# 2025210236.net
KiCad netlist of a schematic drawn in EasyEDA Pro
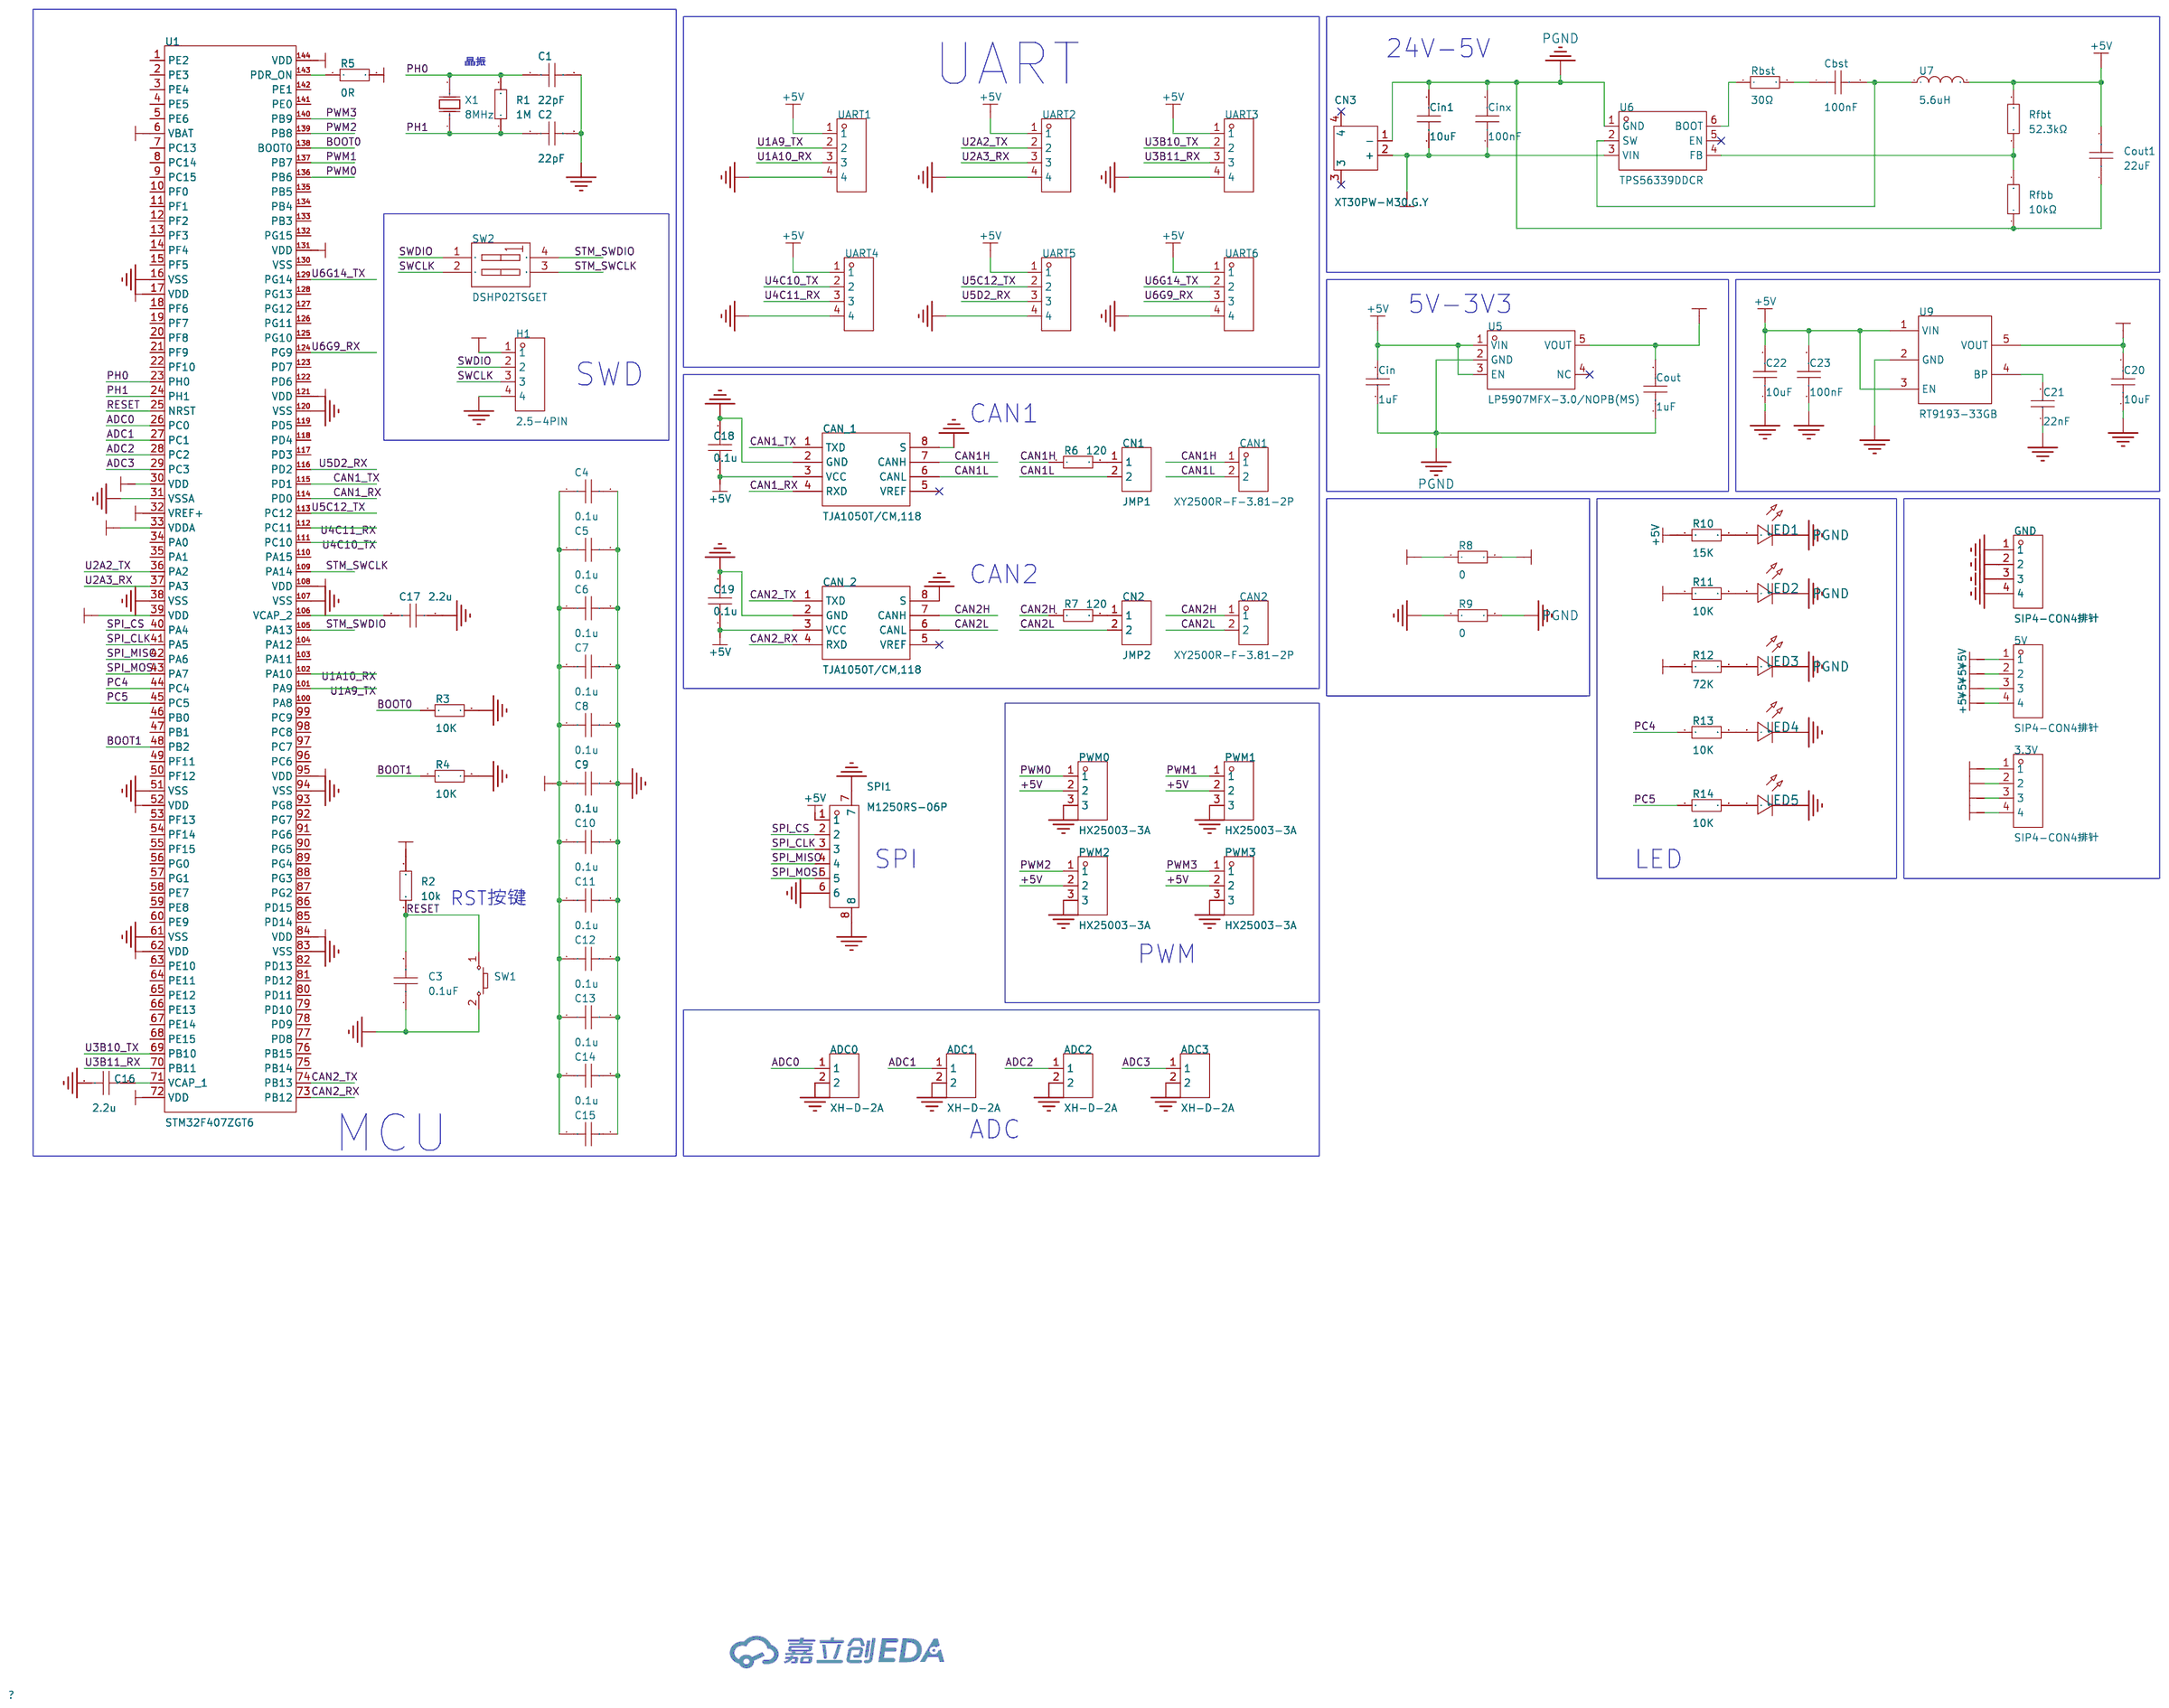
[diagram p0: schematic sheet]

(export (version "E")
  (design (tool "Eeschema 10.0.6"))
  (components
    (comp (ref "3.3V")
      (value "SIP4-CON4排针")
      (footprint "easyedapro:HDR-TH_4P-P2.54-V-M-3")
      (libsource (lib "easyedapro") (part "SIP4-CON4排针"))
    )
    (comp (ref "5V")
      (value "SIP4-CON4排针")
      (footprint "easyedapro:HDR-TH_4P-P2.54-V-M-3")
      (libsource (lib "easyedapro") (part "SIP4-CON4排针"))
    )
    (comp (ref "ADC0")
      (value "XH-D-2A")
      (footprint "easyedapro:CONN-TH_XH-2A")
      (fields (field (name "Manufacturer") "DEALON(德艺隆)"))
      (libsource (lib "easyedapro") (part "XH-D-2A"))
    )
    (comp (ref "ADC1")
      (value "XH-D-2A")
      (footprint "easyedapro:CONN-TH_XH-2A")
      (fields (field (name "Manufacturer") "DEALON(德艺隆)"))
      (libsource (lib "easyedapro") (part "XH-D-2A"))
    )
    (comp (ref "ADC2")
      (value "XH-D-2A")
      (footprint "easyedapro:CONN-TH_XH-2A")
      (fields (field (name "Manufacturer") "DEALON(德艺隆)"))
      (libsource (lib "easyedapro") (part "XH-D-2A"))
    )
    (comp (ref "ADC3")
      (value "XH-D-2A")
      (footprint "easyedapro:CONN-TH_XH-2A")
      (fields (field (name "Manufacturer") "DEALON(德艺隆)"))
      (libsource (lib "easyedapro") (part "XH-D-2A"))
    )
    (comp (ref "C1")
      (value "22pF")
      (footprint "easyedapro:C0603")
      (libsource (lib "easyedapro") (part "Capacitance"))
    )
    (comp (ref "C2")
      (value "22pF")
      (footprint "easyedapro:C0603")
      (libsource (lib "easyedapro") (part "Capacitance"))
    )
    (comp (ref "C3")
      (value "0.1uF")
      (footprint "easyedapro:C0603")
      (libsource (lib "easyedapro") (part "Capacitance"))
    )
    (comp (ref "C4")
      (value "0.1u")
      (footprint "easyedapro:C0603")
      (libsource (lib "easyedapro") (part "Capacitance"))
    )
    (comp (ref "C5")
      (value "0.1u")
      (footprint "easyedapro:C0603")
      (libsource (lib "easyedapro") (part "Capacitance"))
    )
    (comp (ref "C6")
      (value "0.1u")
      (footprint "easyedapro:C0603")
      (libsource (lib "easyedapro") (part "Capacitance"))
    )
    (comp (ref "C7")
      (value "0.1u")
      (footprint "easyedapro:C0603")
      (libsource (lib "easyedapro") (part "Capacitance"))
    )
    (comp (ref "C8")
      (value "0.1u")
      (footprint "easyedapro:C0603")
      (libsource (lib "easyedapro") (part "Capacitance"))
    )
    (comp (ref "C9")
      (value "0.1u")
      (footprint "easyedapro:C0603")
      (libsource (lib "easyedapro") (part "Capacitance"))
    )
    (comp (ref "C10")
      (value "0.1u")
      (footprint "easyedapro:C0603")
      (libsource (lib "easyedapro") (part "Capacitance"))
    )
    (comp (ref "C11")
      (value "0.1u")
      (footprint "easyedapro:C0603")
      (libsource (lib "easyedapro") (part "Capacitance"))
    )
    (comp (ref "C12")
      (value "0.1u")
      (footprint "easyedapro:C0603")
      (libsource (lib "easyedapro") (part "Capacitance"))
    )
    (comp (ref "C13")
      (value "0.1u")
      (footprint "easyedapro:C0603")
      (libsource (lib "easyedapro") (part "Capacitance"))
    )
    (comp (ref "C14")
      (value "0.1u")
      (footprint "easyedapro:C0603")
      (libsource (lib "easyedapro") (part "Capacitance"))
    )
    (comp (ref "C15")
      (value "0.1u")
      (footprint "easyedapro:C0603")
      (libsource (lib "easyedapro") (part "Capacitance"))
    )
    (comp (ref "C16")
      (value "2.2u")
      (footprint "easyedapro:C0603")
      (libsource (lib "easyedapro") (part "Capacitance"))
    )
    (comp (ref "C17")
      (value "2.2u")
      (footprint "easyedapro:C0603")
      (libsource (lib "easyedapro") (part "Capacitance"))
    )
    (comp (ref "C18")
      (value "0.1u")
      (footprint "easyedapro:C0603")
      (libsource (lib "easyedapro") (part "Capacitance"))
    )
    (comp (ref "C19")
      (value "0.1u")
      (footprint "easyedapro:C0603")
      (libsource (lib "easyedapro") (part "Capacitance"))
    )
    (comp (ref "C20")
      (value "10uF")
      (footprint "easyedapro:C0603")
      (description "容值:10uF;精度:±10%;额定电压:10V;温度系数:X5R;")
      (fields
        (field (name "Manufacturer Part") "CGA0603X5R106K100JT")
        (field (name "Manufacturer") "HRE(芯声)")
      )
      (libsource (lib "easyedapro") (part "CGA0603X5R106K100JT"))
    )
    (comp (ref "C21")
      (value "22nF")
      (footprint "easyedapro:C0603")
      (description "容值:22nF;精度:±10%;额定电压:50V;温度系数:X7R;")
      (fields
        (field (name "Manufacturer Part") "CL10B223KB8NNNC")
        (field (name "Manufacturer") "SAMSUNG(三星)")
      )
      (libsource (lib "easyedapro") (part "CL10B223KB8NNNC"))
    )
    (comp (ref "C22")
      (value "10uF")
      (footprint "easyedapro:C0603")
      (description "容值:10uF;精度:±10%;额定电压:10V;温度系数:X5R;")
      (fields
        (field (name "Manufacturer Part") "CGA0603X5R106K100JT")
        (field (name "Manufacturer") "HRE(芯声)")
      )
      (libsource (lib "easyedapro") (part "CGA0603X5R106K100JT"))
    )
    (comp (ref "C23")
      (value "100nF")
      (footprint "easyedapro:C0603")
      (description "容值:100nF;精度:±10%;额定电压:50V;温度系数:X7R;")
      (fields
        (field (name "Manufacturer Part") "CGA0603X7R104K500JT")
        (field (name "Manufacturer") "HRE(芯声)")
      )
      (libsource (lib "easyedapro") (part "CGA0603X7R104K500JT"))
    )
    (comp (ref "CAN1")
      (value "XY2500R-F-3.81-2P")
      (footprint "easyedapro:CONN-TH_XY2500R-F-3.81-2P")
      (description "连接器类型:板端/插座-闭口;结构:1x2P;间距:3.81mm;颜色:绿色;安装方式:弯针;排数:1;每排PIN数:2;额定电流:8A;额定电压:300V;工作温度:-;")
      (fields (field (name "Manufacturer") "XINLAIYA(新莱亚)"))
      (libsource (lib "easyedapro") (part "XY2500R-F-3.81-2P"))
    )
    (comp (ref "CAN2")
      (value "XY2500R-F-3.81-2P")
      (footprint "easyedapro:CONN-TH_XY2500R-F-3.81-2P")
      (description "连接器类型:板端/插座-闭口;结构:1x2P;间距:3.81mm;颜色:绿色;安装方式:弯针;排数:1;每排PIN数:2;额定电流:8A;额定电压:300V;工作温度:-;")
      (fields (field (name "Manufacturer") "XINLAIYA(新莱亚)"))
      (libsource (lib "easyedapro") (part "XY2500R-F-3.81-2P"))
    )
    (comp (ref "CAN_1")
      (value "TJA1050T/CM,118")
      (footprint "easyedapro:SOIC-8_L5.0-W4.0-P1.27-LS6.0-BL")
      (description "类型:-;")
      (fields (field (name "Manufacturer") "NXP(恩智浦)"))
      (libsource (lib "easyedapro") (part "TJA1050T/CM,118"))
    )
    (comp (ref "CAN_2")
      (value "TJA1050T/CM,118")
      (footprint "easyedapro:SOIC-8_L5.0-W4.0-P1.27-LS6.0-BL")
      (description "类型:-;")
      (fields (field (name "Manufacturer") "NXP(恩智浦)"))
      (libsource (lib "easyedapro") (part "TJA1050T/CM,118"))
    )
    (comp (ref "Cbst")
      (value "100nF")
      (footprint "easyedapro:C0805")
      (description "容值:100nF;精度:±20%;额定电压:50V;材质(温度系数):X7R;")
      (fields (field (name "Manufacturer Part") "C0805C104M5RACTU") (field (name "Manufacturer") "KEMET(基美)"))
      (libsource (lib "easyedapro") (part "C0805C104M5RACTU"))
    )
    (comp (ref "Cin")
      (value "1uF")
      (footprint "easyedapro:C0603")
      (description "容值:1uF;精度:±10%;额定电压:16V;温度系数:X7R;")
      (fields
        (field (name "Manufacturer Part") "EMK107B7105KA-T")
        (field (name "Manufacturer") "TAIYO YUDEN(太诱)")
      )
      (libsource (lib "easyedapro") (part "EMK107B7105KA-T"))
    )
    (comp (ref "Cin1")
      (value "10uF")
      (footprint "easyedapro:C0805")
      (description "容值:10uF;精度:±20%;额定电压:25V;温度系数:X5R;")
      (fields
        (field (name "Manufacturer Part") "MSAST21GBB5106MTNA01")
        (field (name "Manufacturer") "TAIYO YUDEN(太诱)")
      )
      (libsource (lib "easyedapro") (part "MSAST21GBB5106MTNA01"))
    )
    (comp (ref "Cinx")
      (value "100nF")
      (footprint "easyedapro:C0805")
      (description "容值:100nF;精度:±20%;额定电压:50V;材质(温度系数):X7R;")
      (fields (field (name "Manufacturer Part") "C0805C104M5RACTU") (field (name "Manufacturer") "KEMET(基美)"))
      (libsource (lib "easyedapro") (part "C0805C104M5RACTU"))
    )
    (comp (ref "CN1")
      (value "JMP1")
      (footprint "easyedapro:HDR-TH_2P-P2.54_C9900022687")
      (libsource (lib "easyedapro") (part "2.54MM间距 针长19MM 2P排针"))
    )
    (comp (ref "CN2")
      (value "JMP2")
      (footprint "easyedapro:HDR-TH_2P-P2.54_C9900022687")
      (libsource (lib "easyedapro") (part "2.54MM间距 针长19MM 2P排针"))
    )
    (comp (ref "CN3")
      (value "XT30PW-M30.G.Y")
      (footprint "easyedapro:CONN-TH_XT30PW-M")
      (description "类别:-;类型1:-;")
      (fields (field (name "Manufacturer") "AMASS(艾迈斯)"))
      (libsource (lib "easyedapro") (part "XT30PW-M"))
    )
    (comp (ref "Cout")
      (value "1uF")
      (footprint "easyedapro:C0402")
      (description "容值:1uF;精度:±10%;额定电压:25V;温度系数:X5R;")
      (fields (field (name "Manufacturer Part") "C1005X5R1E105K050BC") (field (name "Manufacturer") "TDK"))
      (libsource (lib "easyedapro") (part "C1005X5R1E105K050BC"))
    )
    (comp (ref "Cout1")
      (value "22uF")
      (footprint "easyedapro:C0805")
      (description "容值:22uF;精度:±20%;额定电压:10V;温度系数:X5R;")
      (fields (field (name "Manufacturer Part") "C2012X5R1A226M125AB") (field (name "Manufacturer") "TDK"))
      (libsource (lib "easyedapro") (part "C2012X5R1A226M125AB_C2167626"))
    )
    (comp (ref "GND")
      (value "SIP4-CON4排针")
      (footprint "easyedapro:HDR-TH_4P-P2.54-V-M-3")
      (libsource (lib "easyedapro") (part "SIP4-CON4排针"))
    )
    (comp (ref "H1")
      (value "2.5-4PIN")
      (footprint "easyedapro:HDR-TH_4P-P2.54-V-M")
      (libsource (lib "easyedapro") (part "2.5-4PIN"))
    )
    (comp (ref "LED1")
      (value "~")
      (footprint "easyedapro:LED_0603")
      (libsource (lib "easyedapro") (part "LED_R"))
    )
    (comp (ref "LED2")
      (value "~")
      (footprint "easyedapro:LED_0603")
      (libsource (lib "easyedapro") (part "LED_R"))
    )
    (comp (ref "LED3")
      (value "~")
      (footprint "easyedapro:LED_0603")
      (libsource (lib "easyedapro") (part "LED_R"))
    )
    (comp (ref "LED4")
      (value "~")
      (footprint "easyedapro:LED_0603")
      (libsource (lib "easyedapro") (part "LED_R"))
    )
    (comp (ref "LED5")
      (value "~")
      (footprint "easyedapro:LED_0603")
      (libsource (lib "easyedapro") (part "LED_R"))
    )
    (comp (ref "PWM0")
      (value "HX25003-3A")
      (footprint "easyedapro:CONN-TH_3P-P2.50_HX25003-3A")
      (description "插针结构:1x3P;间距:2.5mm;安装方式:直插;参考系列:XH;总PIN数:3P;排数:1;每排PIN数:3;行距:-;额定电流:5A;触头材质:黄铜;工作温度:-25°C~+85°C;")
      (fields (field (name "Manufacturer") "HX(红星)"))
      (libsource (lib "easyedapro") (part "HX25003-3A"))
    )
    (comp (ref "PWM1")
      (value "HX25003-3A")
      (footprint "easyedapro:CONN-TH_3P-P2.50_HX25003-3A")
      (description "插针结构:1x3P;间距:2.5mm;安装方式:直插;参考系列:XH;总PIN数:3P;排数:1;每排PIN数:3;行距:-;额定电流:5A;触头材质:黄铜;工作温度:-25°C~+85°C;")
      (fields (field (name "Manufacturer") "HX(红星)"))
      (libsource (lib "easyedapro") (part "HX25003-3A"))
    )
    (comp (ref "PWM2")
      (value "HX25003-3A")
      (footprint "easyedapro:CONN-TH_3P-P2.50_HX25003-3A")
      (description "插针结构:1x3P;间距:2.5mm;安装方式:直插;参考系列:XH;总PIN数:3P;排数:1;每排PIN数:3;行距:-;额定电流:5A;触头材质:黄铜;工作温度:-25°C~+85°C;")
      (fields (field (name "Manufacturer") "HX(红星)"))
      (libsource (lib "easyedapro") (part "HX25003-3A"))
    )
    (comp (ref "PWM3")
      (value "HX25003-3A")
      (footprint "easyedapro:CONN-TH_3P-P2.50_HX25003-3A")
      (description "插针结构:1x3P;间距:2.5mm;安装方式:直插;参考系列:XH;总PIN数:3P;排数:1;每排PIN数:3;行距:-;额定电流:5A;触头材质:黄铜;工作温度:-25°C~+85°C;")
      (fields (field (name "Manufacturer") "HX(红星)"))
      (libsource (lib "easyedapro") (part "HX25003-3A"))
    )
    (comp (ref "R1") (value "1M") (footprint "easyedapro:R0603") (libsource (lib "easyedapro") (part "电阻")))
    (comp (ref "R2") (value "10k") (footprint "easyedapro:R0603") (libsource (lib "easyedapro") (part "电阻")))
    (comp (ref "R3") (value "10K") (footprint "easyedapro:R0603") (libsource (lib "easyedapro") (part "电阻")))
    (comp (ref "R4") (value "10K") (footprint "easyedapro:R0603") (libsource (lib "easyedapro") (part "电阻")))
    (comp (ref "R5") (value "0R") (footprint "easyedapro:R0603") (libsource (lib "easyedapro") (part "电阻")))
    (comp (ref "R6") (value "120") (footprint "easyedapro:R0603") (libsource (lib "easyedapro") (part "电阻")))
    (comp (ref "R7") (value "120") (footprint "easyedapro:R0603") (libsource (lib "easyedapro") (part "电阻")))
    (comp (ref "R8") (value "0") (footprint "easyedapro:R0603") (libsource (lib "easyedapro") (part "电阻")))
    (comp (ref "R9") (value "0") (footprint "easyedapro:R0603") (libsource (lib "easyedapro") (part "电阻")))
    (comp (ref "R10") (value "15K") (footprint "easyedapro:R0603") (libsource (lib "easyedapro") (part "电阻")))
    (comp (ref "R11") (value "10K") (footprint "easyedapro:R0603") (libsource (lib "easyedapro") (part "电阻")))
    (comp (ref "R12") (value "72K") (footprint "easyedapro:R0603") (libsource (lib "easyedapro") (part "电阻")))
    (comp (ref "R13") (value "10K") (footprint "easyedapro:R0603") (libsource (lib "easyedapro") (part "电阻")))
    (comp (ref "R14") (value "10K") (footprint "easyedapro:R0603") (libsource (lib "easyedapro") (part "电阻")))
    (comp (ref "Rbst")
      (value "30Ω")
      (footprint "easyedapro:R0603")
      (description "电阻类型:厚膜电阻;阻值:30Ω;精度:±1%;功率:100mW;工作电压:75V;温度系数:±100ppm/°C;")
      (fields (field (name "Manufacturer Part") "RC0603FR-0730RL") (field (name "Manufacturer") "YAGEO(国巨)"))
      (libsource (lib "easyedapro") (part "RC0603FR-0730RL"))
    )
    (comp (ref "Rfbb")
      (value "10kΩ")
      (footprint "easyedapro:R0603")
      (description "电阻类型:厚膜电阻;阻值:10kΩ;精度:±1%;功率:100mW;最大工作电压:75V;温度系数:±100ppm/°C;")
      (fields (field (name "Manufacturer Part") "RC0603FR-0710KL") (field (name "Manufacturer") "YAGEO(国巨)"))
      (libsource (lib "easyedapro") (part "RC0603FR-0710KL"))
    )
    (comp (ref "Rfbt")
      (value "52.3kΩ")
      (footprint "easyedapro:R0603")
      (description "电阻类型:厚膜电阻;阻值:52.3kΩ;精度:±1%;功率:100mW;工作电压:75V;温度系数:±100ppm/°C;")
      (fields (field (name "Manufacturer Part") "RC0603FR-0752K3L") (field (name "Manufacturer") "YAGEO(国巨)"))
      (libsource (lib "easyedapro") (part "RC0603FR-0752K3L"))
    )
    (comp (ref "SPI1")
      (value "M1250RS-06P")
      (footprint "easyedapro:CONN-SMD_M1250RS-06P")
      (description "插针结构:1x6P;间距:1.25mm;安装方式:卧贴;参考系列:-;总PIN数:6P;排数:1;每排PIN数:6;行距:-;额定电流:1A;工作温度:-25°C~+85°C;")
      (fields (field (name "Manufacturer") "XFCN(兴飞)"))
      (libsource (lib "easyedapro") (part "M1250RS-06P"))
    )
    (comp (ref "SW1")
      (value "~")
      (footprint "easyedapro:Key_SMD_3x4x2")
      (libsource (lib "easyedapro") (part "轻触按键x2"))
    )
    (comp (ref "SW2")
      (value "DSHP02TSGET")
      (footprint "easyedapro:SW-SMD_4P_DSHP02TSGET")
      (description "类型:平拨,凹槽式;电路结构:单刀单掷;开关位数:2位;工作寿命:-;颜色:黑色;")
      (fields (field (name "Manufacturer") "YE"))
      (libsource (lib "easyedapro") (part "DSHP02TSGET"))
    )
    (comp (ref "U1")
      (value "STM32F407ZGT6")
      (footprint "easyedapro:LQFP-144_L20.0-W20.0-P0.50-LS22.0-BL")
      (description "CPU内核:ARM-M4;CPU最大主频:168MHz;应用领域:-;")
      (fields (field (name "Manufacturer") "ST(意法半导体)"))
      (libsource (lib "easyedapro") (part "STM32F407ZGT6"))
    )
    (comp (ref "U5")
      (value "LP5907MFX-3.0/NOPB(MS)")
      (footprint "easyedapro:SOT-23-5_L2.9-W1.6-P0.95-LS2.8-BR")
      (description "输出类型:固定;最大输入电压:5.5V;输出电压:3V;输出电流:300mA;电源纹波抑制比(PSRR):-;输出极性:正极;")
      (fields (field (name "Manufacturer") "MSKSEMI(美森科)"))
      (libsource (lib "easyedapro") (part "LP5907MFX-3.0/NOPB(MS)"))
    )
    (comp (ref "U6")
      (value "TPS56339DDCR")
      (footprint "easyedapro:TSOT-23-6_L2.9-W1.6-P0.95-LS2.8-BR")
      (description "功能类型:降压型;输出类型:可调;输入电压:4.5V~24V;输出电压:800mV~16V;输出电流:3A;")
      (fields (field (name "Manufacturer") "TI(德州仪器)"))
      (libsource (lib "easyedapro") (part "TPS56339DDCR"))
    )
    (comp (ref "U7")
      (value "5.6uH")
      (footprint "easyedapro:IND-SMD_L13.0-W13.0-SDR1307-XXXXX")
      (description "电感值:5.6uH;精度:±20%;额定电流:6.5A;饱和电流(Isat):11A;类型:-;")
      (fields (field (name "Manufacturer Part") "SDR1307-5R6ML") (field (name "Manufacturer") "BOURNS"))
      (libsource (lib "easyedapro") (part "SDR1307-5R6ML"))
    )
    (comp (ref "U9")
      (value "RT9193-33GB")
      (footprint "easyedapro:SOT-23-5_L3.0-W1.7-P0.95-LS2.8-BL")
      (description "输出类型:固定;工作电压:5.5V;输出电压:3.3V;输出电流:300mA;电源纹波抑制比(PSRR):-50dB@(10kHz);输出极性:正极;")
      (fields (field (name "Manufacturer") "RICHTEK(立锜)"))
      (libsource (lib "easyedapro") (part "RT9193-33GB"))
    )
    (comp (ref "UART1")
      (value "SIP4-CON4排针")
      (footprint "easyedapro:HDR-TH_4P-P2.54-V-M-3")
      (libsource (lib "easyedapro") (part "SIP4-CON4排针"))
    )
    (comp (ref "UART2")
      (value "SIP4-CON4排针")
      (footprint "easyedapro:HDR-TH_4P-P2.54-V-M-3")
      (libsource (lib "easyedapro") (part "SIP4-CON4排针"))
    )
    (comp (ref "UART3")
      (value "SIP4-CON4排针")
      (footprint "easyedapro:HDR-TH_4P-P2.54-V-M-3")
      (libsource (lib "easyedapro") (part "SIP4-CON4排针"))
    )
    (comp (ref "UART4")
      (value "SIP4-CON4排针")
      (footprint "easyedapro:HDR-TH_4P-P2.54-V-M-3")
      (libsource (lib "easyedapro") (part "SIP4-CON4排针"))
    )
    (comp (ref "UART5")
      (value "SIP4-CON4排针")
      (footprint "easyedapro:HDR-TH_4P-P2.54-V-M-3")
      (libsource (lib "easyedapro") (part "SIP4-CON4排针"))
    )
    (comp (ref "UART6")
      (value "SIP4-CON4排针")
      (footprint "easyedapro:HDR-TH_4P-P2.54-V-M-3")
      (libsource (lib "easyedapro") (part "SIP4-CON4排针"))
    )
    (comp (ref "X1")
      (value "8MHz")
      (footprint "easyedapro:CRYSTAL-SMD_L5.0-W3.2")
      (description "晶振类型:贴片晶振;频率:8MHz;常温频差:±10ppm;负载电容:20pF;频率稳定度:±20ppm;")
      (fields (field (name "Manufacturer Part") "X50328MSB2GI") (field (name "Manufacturer") "YXC(扬兴晶振)"))
      (libsource (lib "easyedapro") (part "X50328MSB2GI"))
    )
  )
  (nets
    (net (code "1") (name "+5V") (class "Default")
      (node (ref "5V") (pin "1") (pinfunction "1_1") (pintype "unspecified"))
      (node (ref "5V") (pin "2") (pinfunction "2_2") (pintype "unspecified"))
      (node (ref "5V") (pin "3") (pinfunction "3_3") (pintype "unspecified"))
      (node (ref "5V") (pin "4") (pinfunction "4_4") (pintype "unspecified"))
      (node (ref "C18") (pin "1") (pinfunction "1_1") (pintype "input"))
      (node (ref "C19") (pin "1") (pinfunction "1_1") (pintype "input"))
      (node (ref "C22") (pin "2") (pinfunction "2_2") (pintype "unspecified"))
      (node (ref "C23") (pin "2") (pinfunction "2_2") (pintype "unspecified"))
      (node (ref "CAN_1") (pin "3") (pinfunction "VCC_3") (pintype "unspecified"))
      (node (ref "CAN_2") (pin "3") (pinfunction "VCC_3") (pintype "unspecified"))
      (node (ref "Cin") (pin "2") (pinfunction "2_2") (pintype "input"))
      (node (ref "Cout1") (pin "2") (pinfunction "2_2") (pintype "unspecified"))
      (node (ref "PWM0") (pin "2") (pinfunction "2_2") (pintype "unspecified"))
      (node (ref "PWM1") (pin "2") (pinfunction "2_2") (pintype "unspecified"))
      (node (ref "PWM2") (pin "2") (pinfunction "2_2") (pintype "unspecified"))
      (node (ref "PWM3") (pin "2") (pinfunction "2_2") (pintype "unspecified"))
      (node (ref "R10") (pin "1") (pinfunction "1_1") (pintype "input"))
      (node (ref "Rfbt") (pin "2") (pinfunction "2_2") (pintype "unspecified"))
      (node (ref "SPI1") (pin "1") (pinfunction "1_1") (pintype "unspecified"))
      (node (ref "U5") (pin "1") (pinfunction "VIN_1") (pintype "unspecified"))
      (node (ref "U5") (pin "3") (pinfunction "EN_3") (pintype "unspecified"))
      (node (ref "U7") (pin "2") (pinfunction "2_2") (pintype "unspecified"))
      (node (ref "U9") (pin "1") (pinfunction "VIN_1") (pintype "unspecified"))
      (node (ref "U9") (pin "3") (pinfunction "EN_3") (pintype "unspecified"))
      (node (ref "UART1") (pin "1") (pinfunction "1_1") (pintype "unspecified"))
      (node (ref "UART2") (pin "1") (pinfunction "1_1") (pintype "unspecified"))
      (node (ref "UART3") (pin "1") (pinfunction "1_1") (pintype "unspecified"))
      (node (ref "UART4") (pin "1") (pinfunction "1_1") (pintype "unspecified"))
      (node (ref "UART5") (pin "1") (pinfunction "1_1") (pintype "unspecified"))
      (node (ref "UART6") (pin "1") (pinfunction "1_1") (pintype "unspecified"))
    )
    (net (code "2") (name "/ADC0") (class "Default")
      (node (ref "ADC0") (pin "1") (pinfunction "1_1") (pintype "unspecified"))
      (node (ref "U1") (pin "26") (pinfunction "PC0_26") (pintype "unspecified"))
    )
    (net (code "3") (name "/ADC1") (class "Default")
      (node (ref "ADC1") (pin "1") (pinfunction "1_1") (pintype "unspecified"))
      (node (ref "U1") (pin "27") (pinfunction "PC1_27") (pintype "unspecified"))
    )
    (net (code "4") (name "/ADC2") (class "Default")
      (node (ref "ADC2") (pin "1") (pinfunction "1_1") (pintype "unspecified"))
      (node (ref "U1") (pin "28") (pinfunction "PC2_28") (pintype "unspecified"))
    )
    (net (code "5") (name "/ADC3") (class "Default")
      (node (ref "ADC3") (pin "1") (pinfunction "1_1") (pintype "unspecified"))
      (node (ref "U1") (pin "29") (pinfunction "PC3_29") (pintype "unspecified"))
    )
    (net (code "6") (name "/BOOT0") (class "Default")
      (node (ref "R3") (pin "1") (pinfunction "1_1") (pintype "input"))
      (node (ref "U1") (pin "138") (pinfunction "BOOT0_138") (pintype "unspecified"))
    )
    (net (code "7") (name "/BOOT1") (class "Default")
      (node (ref "R4") (pin "1") (pinfunction "1_1") (pintype "input"))
      (node (ref "U1") (pin "48") (pinfunction "PB2_48") (pintype "unspecified"))
    )
    (net (code "8") (name "/CAN1H") (class "Default")
      (node (ref "CAN1") (pin "1") (pinfunction "1_1") (pintype "unspecified"))
      (node (ref "CAN_1") (pin "7") (pinfunction "CANH_7") (pintype "unspecified"))
      (node (ref "R6") (pin "1") (pinfunction "1_1") (pintype "input"))
    )
    (net (code "9") (name "/CAN1L") (class "Default")
      (node (ref "CAN1") (pin "2") (pinfunction "2_2") (pintype "unspecified"))
      (node (ref "CAN_1") (pin "6") (pinfunction "CANL_6") (pintype "unspecified"))
      (node (ref "CN1") (pin "2") (pinfunction "2_2") (pintype "unspecified"))
    )
    (net (code "10") (name "/CAN1_RX") (class "Default")
      (node (ref "CAN_1") (pin "4") (pinfunction "RXD_4") (pintype "unspecified"))
      (node (ref "U1") (pin "114") (pinfunction "PD0_114") (pintype "unspecified"))
    )
    (net (code "11") (name "/CAN1_TX") (class "Default")
      (node (ref "CAN_1") (pin "1") (pinfunction "TXD_1") (pintype "unspecified"))
      (node (ref "U1") (pin "115") (pinfunction "PD1_115") (pintype "unspecified"))
    )
    (net (code "12") (name "/CAN2H") (class "Default")
      (node (ref "CAN2") (pin "1") (pinfunction "1_1") (pintype "unspecified"))
      (node (ref "CAN_2") (pin "7") (pinfunction "CANH_7") (pintype "unspecified"))
      (node (ref "R7") (pin "1") (pinfunction "1_1") (pintype "input"))
    )
    (net (code "13") (name "/CAN2L") (class "Default")
      (node (ref "CAN2") (pin "2") (pinfunction "2_2") (pintype "unspecified"))
      (node (ref "CAN_2") (pin "6") (pinfunction "CANL_6") (pintype "unspecified"))
      (node (ref "CN2") (pin "2") (pinfunction "2_2") (pintype "unspecified"))
    )
    (net (code "14") (name "/CAN2_RX") (class "Default")
      (node (ref "CAN_2") (pin "4") (pinfunction "RXD_4") (pintype "unspecified"))
      (node (ref "U1") (pin "73") (pinfunction "PB12_73") (pintype "unspecified"))
    )
    (net (code "15") (name "/CAN2_TX") (class "Default")
      (node (ref "CAN_2") (pin "1") (pinfunction "TXD_1") (pintype "unspecified"))
      (node (ref "U1") (pin "74") (pinfunction "PB13_74") (pintype "unspecified"))
    )
    (net (code "16") (name "/PC4") (class "Default")
      (node (ref "R13") (pin "1") (pinfunction "1_1") (pintype "input"))
      (node (ref "U1") (pin "44") (pinfunction "PC4_44") (pintype "unspecified"))
    )
    (net (code "17") (name "/PC5") (class "Default")
      (node (ref "R14") (pin "1") (pinfunction "1_1") (pintype "input"))
      (node (ref "U1") (pin "45") (pinfunction "PC5_45") (pintype "unspecified"))
    )
    (net (code "18") (name "/PH0") (class "Default")
      (node (ref "C1") (pin "1") (pinfunction "1_1") (pintype "input"))
      (node (ref "R1") (pin "2") (pinfunction "2_2") (pintype "input"))
      (node (ref "U1") (pin "23") (pinfunction "PH0_23") (pintype "unspecified"))
      (node (ref "X1") (pin "2") (pinfunction "OSC2_2") (pintype "input"))
    )
    (net (code "19") (name "/PH1") (class "Default")
      (node (ref "C2") (pin "1") (pinfunction "1_1") (pintype "input"))
      (node (ref "R1") (pin "1") (pinfunction "1_1") (pintype "input"))
      (node (ref "U1") (pin "24") (pinfunction "PH1_24") (pintype "unspecified"))
      (node (ref "X1") (pin "1") (pinfunction "OSC1_1") (pintype "input"))
    )
    (net (code "20") (name "/PWM0") (class "Default")
      (node (ref "PWM0") (pin "1") (pinfunction "1_1") (pintype "unspecified"))
      (node (ref "U1") (pin "136") (pinfunction "PB6_136") (pintype "unspecified"))
    )
    (net (code "21") (name "/PWM1") (class "Default")
      (node (ref "PWM1") (pin "1") (pinfunction "1_1") (pintype "unspecified"))
      (node (ref "U1") (pin "137") (pinfunction "PB7_137") (pintype "unspecified"))
    )
    (net (code "22") (name "/PWM2") (class "Default")
      (node (ref "PWM2") (pin "1") (pinfunction "1_1") (pintype "unspecified"))
      (node (ref "U1") (pin "139") (pinfunction "PB8_139") (pintype "unspecified"))
    )
    (net (code "23") (name "/PWM3") (class "Default")
      (node (ref "PWM3") (pin "1") (pinfunction "1_1") (pintype "unspecified"))
      (node (ref "U1") (pin "140") (pinfunction "PB9_140") (pintype "unspecified"))
    )
    (net (code "24") (name "/RESET") (class "Default")
      (node (ref "C3") (pin "2") (pinfunction "2_2") (pintype "input"))
      (node (ref "R2") (pin "1") (pinfunction "1_1") (pintype "input"))
      (node (ref "SW1") (pin "1") (pinfunction "1_1") (pintype "input"))
      (node (ref "U1") (pin "25") (pinfunction "NRST_25") (pintype "unspecified"))
    )
    (net (code "25") (name "/SPI_CLK") (class "Default")
      (node (ref "SPI1") (pin "3") (pinfunction "3_3") (pintype "unspecified"))
      (node (ref "U1") (pin "41") (pinfunction "PA5_41") (pintype "unspecified"))
    )
    (net (code "26") (name "/SPI_CS") (class "Default")
      (node (ref "SPI1") (pin "2") (pinfunction "2_2") (pintype "unspecified"))
      (node (ref "U1") (pin "40") (pinfunction "PA4_40") (pintype "unspecified"))
    )
    (net (code "27") (name "/SPI_MISO") (class "Default")
      (node (ref "SPI1") (pin "4") (pinfunction "4_4") (pintype "unspecified"))
      (node (ref "U1") (pin "42") (pinfunction "PA6_42") (pintype "unspecified"))
    )
    (net (code "28") (name "/SPI_MOSI") (class "Default")
      (node (ref "SPI1") (pin "5") (pinfunction "5_5") (pintype "unspecified"))
      (node (ref "U1") (pin "43") (pinfunction "PA7_43") (pintype "unspecified"))
    )
    (net (code "29") (name "/STM_SWCLK") (class "Default")
      (node (ref "SW2") (pin "3") (pinfunction "B2_3") (pintype "input"))
      (node (ref "U1") (pin "109") (pinfunction "PA14_109") (pintype "unspecified"))
    )
    (net (code "30") (name "/STM_SWDIO") (class "Default")
      (node (ref "SW2") (pin "4") (pinfunction "B1_4") (pintype "input"))
      (node (ref "U1") (pin "105") (pinfunction "PA13_105") (pintype "unspecified"))
    )
    (net (code "31") (name "/SWCLK") (class "Default")
      (node (ref "H1") (pin "3") (pinfunction "3_3") (pintype "unspecified"))
      (node (ref "SW2") (pin "2") (pinfunction "A2_2") (pintype "input"))
    )
    (net (code "32") (name "/SWDIO") (class "Default")
      (node (ref "H1") (pin "2") (pinfunction "2_2") (pintype "unspecified"))
      (node (ref "SW2") (pin "1") (pinfunction "A1_1") (pintype "input"))
    )
    (net (code "33") (name "/U1A9_TX") (class "Default")
      (node (ref "U1") (pin "101") (pinfunction "PA9_101") (pintype "unspecified"))
      (node (ref "UART1") (pin "2") (pinfunction "2_2") (pintype "unspecified"))
    )
    (net (code "34") (name "/U1A10_RX") (class "Default")
      (node (ref "U1") (pin "102") (pinfunction "PA10_102") (pintype "unspecified"))
      (node (ref "UART1") (pin "3") (pinfunction "3_3") (pintype "unspecified"))
    )
    (net (code "35") (name "/U2A2_TX") (class "Default")
      (node (ref "U1") (pin "36") (pinfunction "PA2_36") (pintype "unspecified"))
      (node (ref "UART2") (pin "2") (pinfunction "2_2") (pintype "unspecified"))
    )
    (net (code "36") (name "/U2A3_RX") (class "Default")
      (node (ref "U1") (pin "37") (pinfunction "PA3_37") (pintype "unspecified"))
      (node (ref "UART2") (pin "3") (pinfunction "3_3") (pintype "unspecified"))
    )
    (net (code "37") (name "/U3B10_TX") (class "Default")
      (node (ref "U1") (pin "69") (pinfunction "PB10_69") (pintype "unspecified"))
      (node (ref "UART3") (pin "2") (pinfunction "2_2") (pintype "unspecified"))
    )
    (net (code "38") (name "/U3B11_RX") (class "Default")
      (node (ref "U1") (pin "70") (pinfunction "PB11_70") (pintype "unspecified"))
      (node (ref "UART3") (pin "3") (pinfunction "3_3") (pintype "unspecified"))
    )
    (net (code "39") (name "/U4C10_TX") (class "Default")
      (node (ref "U1") (pin "111") (pinfunction "PC10_111") (pintype "unspecified"))
      (node (ref "UART4") (pin "2") (pinfunction "2_2") (pintype "unspecified"))
    )
    (net (code "40") (name "/U4C11_RX") (class "Default")
      (node (ref "U1") (pin "112") (pinfunction "PC11_112") (pintype "unspecified"))
      (node (ref "UART4") (pin "3") (pinfunction "3_3") (pintype "unspecified"))
    )
    (net (code "41") (name "/U5C12_TX") (class "Default")
      (node (ref "U1") (pin "113") (pinfunction "PC12_113") (pintype "unspecified"))
      (node (ref "UART5") (pin "2") (pinfunction "2_2") (pintype "unspecified"))
    )
    (net (code "42") (name "/U5D2_RX") (class "Default")
      (node (ref "U1") (pin "116") (pinfunction "PD2_116") (pintype "unspecified"))
      (node (ref "UART5") (pin "3") (pinfunction "3_3") (pintype "unspecified"))
    )
    (net (code "43") (name "/U6G9_RX") (class "Default")
      (node (ref "U1") (pin "124") (pinfunction "PG9_124") (pintype "unspecified"))
      (node (ref "UART6") (pin "3") (pinfunction "3_3") (pintype "unspecified"))
    )
    (net (code "44") (name "/U6G14_TX") (class "Default")
      (node (ref "U1") (pin "129") (pinfunction "PG14_129") (pintype "unspecified"))
      (node (ref "UART6") (pin "2") (pinfunction "2_2") (pintype "unspecified"))
    )
    (net (code "45") (name "3.3V") (class "Default")
      (node (ref "3.3V") (pin "1") (pinfunction "1_1") (pintype "unspecified"))
      (node (ref "3.3V") (pin "2") (pinfunction "2_2") (pintype "unspecified"))
      (node (ref "3.3V") (pin "3") (pinfunction "3_3") (pintype "unspecified"))
      (node (ref "3.3V") (pin "4") (pinfunction "4_4") (pintype "unspecified"))
      (node (ref "Cout") (pin "2") (pinfunction "2_2") (pintype "unspecified"))
      (node (ref "R11") (pin "1") (pinfunction "1_1") (pintype "input"))
      (node (ref "R8") (pin "2") (pinfunction "2_2") (pintype "input"))
      (node (ref "U5") (pin "5") (pinfunction "VOUT_5") (pintype "unspecified"))
    )
    (net (code "46") (name "24V") (class "Default")
      (node (ref "CN3") (pin "2") (pinfunction "+_2") (pintype "unspecified"))
      (node (ref "Cin1") (pin "1") (pinfunction "1_1") (pintype "unspecified"))
      (node (ref "Cinx") (pin "1") (pinfunction "1_1") (pintype "unspecified"))
      (node (ref "R12") (pin "1") (pinfunction "1_1") (pintype "input"))
      (node (ref "U6") (pin "3") (pinfunction "VIN_3") (pintype "unspecified"))
    )
    (net (code "47") (name "GND") (class "Default")
      (node (ref "ADC0") (pin "2") (pinfunction "2_2") (pintype "unspecified"))
      (node (ref "ADC1") (pin "2") (pinfunction "2_2") (pintype "unspecified"))
      (node (ref "ADC2") (pin "2") (pinfunction "2_2") (pintype "unspecified"))
      (node (ref "ADC3") (pin "2") (pinfunction "2_2") (pintype "unspecified"))
      (node (ref "C1") (pin "2") (pinfunction "2_2") (pintype "input"))
      (node (ref "C10") (pin "2") (pinfunction "2_2") (pintype "input"))
      (node (ref "C11") (pin "2") (pinfunction "2_2") (pintype "input"))
      (node (ref "C12") (pin "2") (pinfunction "2_2") (pintype "input"))
      (node (ref "C13") (pin "2") (pinfunction "2_2") (pintype "input"))
      (node (ref "C14") (pin "2") (pinfunction "2_2") (pintype "input"))
      (node (ref "C15") (pin "2") (pinfunction "2_2") (pintype "input"))
      (node (ref "C16") (pin "1") (pinfunction "1_1") (pintype "input"))
      (node (ref "C17") (pin "2") (pinfunction "2_2") (pintype "input"))
      (node (ref "C18") (pin "2") (pinfunction "2_2") (pintype "input"))
      (node (ref "C19") (pin "2") (pinfunction "2_2") (pintype "input"))
      (node (ref "C2") (pin "2") (pinfunction "2_2") (pintype "input"))
      (node (ref "C20") (pin "1") (pinfunction "1_1") (pintype "unspecified"))
      (node (ref "C21") (pin "1") (pinfunction "1_1") (pintype "input"))
      (node (ref "C22") (pin "1") (pinfunction "1_1") (pintype "unspecified"))
      (node (ref "C23") (pin "1") (pinfunction "1_1") (pintype "unspecified"))
      (node (ref "C3") (pin "1") (pinfunction "1_1") (pintype "input"))
      (node (ref "C4") (pin "2") (pinfunction "2_2") (pintype "input"))
      (node (ref "C5") (pin "2") (pinfunction "2_2") (pintype "input"))
      (node (ref "C6") (pin "2") (pinfunction "2_2") (pintype "input"))
      (node (ref "C7") (pin "2") (pinfunction "2_2") (pintype "input"))
      (node (ref "C8") (pin "2") (pinfunction "2_2") (pintype "input"))
      (node (ref "C9") (pin "2") (pinfunction "2_2") (pintype "input"))
      (node (ref "CAN_1") (pin "2") (pinfunction "GND_2") (pintype "unspecified"))
      (node (ref "CAN_1") (pin "8") (pinfunction "S_8") (pintype "unspecified"))
      (node (ref "CAN_2") (pin "2") (pinfunction "GND_2") (pintype "unspecified"))
      (node (ref "CAN_2") (pin "8") (pinfunction "S_8") (pintype "unspecified"))
      (node (ref "GND") (pin "1") (pinfunction "1_1") (pintype "unspecified"))
      (node (ref "GND") (pin "2") (pinfunction "2_2") (pintype "unspecified"))
      (node (ref "GND") (pin "3") (pinfunction "3_3") (pintype "unspecified"))
      (node (ref "GND") (pin "4") (pinfunction "4_4") (pintype "unspecified"))
      (node (ref "H1") (pin "4") (pinfunction "4_4") (pintype "unspecified"))
      (node (ref "LED4") (pin "1") (pinfunction "C_1") (pintype "input"))
      (node (ref "LED5") (pin "1") (pinfunction "C_1") (pintype "input"))
      (node (ref "PWM0") (pin "3") (pinfunction "3_3") (pintype "unspecified"))
      (node (ref "PWM1") (pin "3") (pinfunction "3_3") (pintype "unspecified"))
      (node (ref "PWM2") (pin "3") (pinfunction "3_3") (pintype "unspecified"))
      (node (ref "PWM3") (pin "3") (pinfunction "3_3") (pintype "unspecified"))
      (node (ref "R3") (pin "2") (pinfunction "2_2") (pintype "input"))
      (node (ref "R4") (pin "2") (pinfunction "2_2") (pintype "input"))
      (node (ref "R9") (pin "1") (pinfunction "1_1") (pintype "input"))
      (node (ref "SPI1") (pin "6") (pinfunction "6_6") (pintype "unspecified"))
      (node (ref "SPI1") (pin "7") (pinfunction "7_7") (pintype "unspecified"))
      (node (ref "SPI1") (pin "8") (pinfunction "8_8") (pintype "unspecified"))
      (node (ref "SW1") (pin "2") (pinfunction "2_2") (pintype "input"))
      (node (ref "U1") (pin "107") (pinfunction "VSS_107") (pintype "unspecified"))
      (node (ref "U1") (pin "120") (pinfunction "VSS_120") (pintype "unspecified"))
      (node (ref "U1") (pin "16") (pinfunction "VSS_16") (pintype "unspecified"))
      (node (ref "U1") (pin "31") (pinfunction "VSSA_31") (pintype "unspecified"))
      (node (ref "U1") (pin "38") (pinfunction "VSS_38") (pintype "unspecified"))
      (node (ref "U1") (pin "51") (pinfunction "VSS_51") (pintype "unspecified"))
      (node (ref "U1") (pin "61") (pinfunction "VSS_61") (pintype "unspecified"))
      (node (ref "U1") (pin "83") (pinfunction "VSS_83") (pintype "unspecified"))
      (node (ref "U1") (pin "94") (pinfunction "VSS_94") (pintype "unspecified"))
      (node (ref "U9") (pin "2") (pinfunction "GND_2") (pintype "unspecified"))
      (node (ref "UART1") (pin "4") (pinfunction "4_4") (pintype "unspecified"))
      (node (ref "UART2") (pin "4") (pinfunction "4_4") (pintype "unspecified"))
      (node (ref "UART3") (pin "4") (pinfunction "4_4") (pintype "unspecified"))
      (node (ref "UART4") (pin "4") (pinfunction "4_4") (pintype "unspecified"))
      (node (ref "UART5") (pin "4") (pinfunction "4_4") (pintype "unspecified"))
      (node (ref "UART6") (pin "4") (pinfunction "4_4") (pintype "unspecified"))
    )
    (net (code "48") (name "Net-(CN1-Pad1)") (class "Default")
      (node (ref "CN1") (pin "1") (pinfunction "1_1") (pintype "unspecified"))
      (node (ref "R6") (pin "2") (pinfunction "2_2") (pintype "input"))
    )
    (net (code "49") (name "Net-(CN2-Pad1)") (class "Default")
      (node (ref "CN2") (pin "1") (pinfunction "1_1") (pintype "unspecified"))
      (node (ref "R7") (pin "2") (pinfunction "2_2") (pintype "input"))
    )
    (net (code "50") (name "Net-(Cbst-Pad1)") (class "Default")
      (node (ref "Cbst") (pin "1") (pinfunction "1_1") (pintype "unspecified"))
      (node (ref "Rbst") (pin "2") (pinfunction "2_2") (pintype "input"))
    )
    (net (code "51") (name "Net-(LED1-A)") (class "Default")
      (node (ref "LED1") (pin "2") (pinfunction "A_2") (pintype "input"))
      (node (ref "R10") (pin "2") (pinfunction "2_2") (pintype "input"))
    )
    (net (code "52") (name "Net-(LED2-A)") (class "Default")
      (node (ref "LED2") (pin "2") (pinfunction "A_2") (pintype "input"))
      (node (ref "R11") (pin "2") (pinfunction "2_2") (pintype "input"))
    )
    (net (code "53") (name "Net-(LED3-A)") (class "Default")
      (node (ref "LED3") (pin "2") (pinfunction "A_2") (pintype "input"))
      (node (ref "R12") (pin "2") (pinfunction "2_2") (pintype "input"))
    )
    (net (code "54") (name "Net-(LED4-A)") (class "Default")
      (node (ref "LED4") (pin "2") (pinfunction "A_2") (pintype "input"))
      (node (ref "R13") (pin "2") (pinfunction "2_2") (pintype "input"))
    )
    (net (code "55") (name "Net-(LED5-A)") (class "Default")
      (node (ref "LED5") (pin "2") (pinfunction "A_2") (pintype "input"))
      (node (ref "R14") (pin "2") (pinfunction "2_2") (pintype "input"))
    )
    (net (code "56") (name "Net-(U1-PDR_ON)") (class "Default")
      (node (ref "R5") (pin "1") (pinfunction "1_1") (pintype "input"))
      (node (ref "U1") (pin "143") (pinfunction "PDR_ON_143") (pintype "unspecified"))
    )
    (net (code "57") (name "Net-(U1-VCAP_1)") (class "Default")
      (node (ref "C16") (pin "2") (pinfunction "2_2") (pintype "input"))
      (node (ref "U1") (pin "71") (pinfunction "VCAP_1_71") (pintype "unspecified"))
    )
    (net (code "58") (name "Net-(U1-VCAP_2)") (class "Default")
      (node (ref "C17") (pin "1") (pinfunction "1_1") (pintype "input"))
      (node (ref "U1") (pin "106") (pinfunction "VCAP_2_106") (pintype "unspecified"))
    )
    (net (code "59") (name "Net-(U6-BOOT)") (class "Default")
      (node (ref "Rbst") (pin "1") (pinfunction "1_1") (pintype "input"))
      (node (ref "U6") (pin "6") (pinfunction "BOOT_6") (pintype "unspecified"))
    )
    (net (code "60") (name "Net-(U6-FB)") (class "Default")
      (node (ref "Rfbb") (pin "2") (pinfunction "2_2") (pintype "input"))
      (node (ref "Rfbt") (pin "1") (pinfunction "1_1") (pintype "unspecified"))
      (node (ref "U6") (pin "4") (pinfunction "FB_4") (pintype "unspecified"))
    )
    (net (code "61") (name "Net-(U6-SW)") (class "Default")
      (node (ref "Cbst") (pin "2") (pinfunction "2_2") (pintype "unspecified"))
      (node (ref "U6") (pin "2") (pinfunction "SW_2") (pintype "unspecified"))
      (node (ref "U7") (pin "1") (pinfunction "1_1") (pintype "unspecified"))
    )
    (net (code "62") (name "Net-(U9-BP)") (class "Default")
      (node (ref "C21") (pin "2") (pinfunction "2_2") (pintype "input"))
      (node (ref "U9") (pin "4") (pinfunction "BP_4") (pintype "unspecified"))
    )
    (net (code "63") (name "PGND") (class "Default")
      (node (ref "CN3") (pin "1") (pinfunction "-_1") (pintype "unspecified"))
      (node (ref "Cin") (pin "1") (pinfunction "1_1") (pintype "input"))
      (node (ref "Cin1") (pin "2") (pinfunction "2_2") (pintype "unspecified"))
      (node (ref "Cinx") (pin "2") (pinfunction "2_2") (pintype "unspecified"))
      (node (ref "Cout") (pin "1") (pinfunction "1_1") (pintype "unspecified"))
      (node (ref "Cout1") (pin "1") (pinfunction "1_1") (pintype "unspecified"))
      (node (ref "LED1") (pin "1") (pinfunction "C_1") (pintype "input"))
      (node (ref "LED2") (pin "1") (pinfunction "C_1") (pintype "input"))
      (node (ref "LED3") (pin "1") (pinfunction "C_1") (pintype "input"))
      (node (ref "R9") (pin "2") (pinfunction "2_2") (pintype "input"))
      (node (ref "Rfbb") (pin "1") (pinfunction "1_1") (pintype "input"))
      (node (ref "U5") (pin "2") (pinfunction "GND_2") (pintype "unspecified"))
      (node (ref "U6") (pin "1") (pinfunction "GND_1") (pintype "unspecified"))
    )
    (net (code "64") (name "VDD") (class "Default")
      (node (ref "C10") (pin "1") (pinfunction "1_1") (pintype "input"))
      (node (ref "C11") (pin "1") (pinfunction "1_1") (pintype "input"))
      (node (ref "C12") (pin "1") (pinfunction "1_1") (pintype "input"))
      (node (ref "C13") (pin "1") (pinfunction "1_1") (pintype "input"))
      (node (ref "C14") (pin "1") (pinfunction "1_1") (pintype "input"))
      (node (ref "C15") (pin "1") (pinfunction "1_1") (pintype "input"))
      (node (ref "C4") (pin "1") (pinfunction "1_1") (pintype "input"))
      (node (ref "C5") (pin "1") (pinfunction "1_1") (pintype "input"))
      (node (ref "C6") (pin "1") (pinfunction "1_1") (pintype "input"))
      (node (ref "C7") (pin "1") (pinfunction "1_1") (pintype "input"))
      (node (ref "C8") (pin "1") (pinfunction "1_1") (pintype "input"))
      (node (ref "C9") (pin "1") (pinfunction "1_1") (pintype "input"))
      (node (ref "H1") (pin "1") (pinfunction "1_1") (pintype "unspecified"))
      (node (ref "R2") (pin "2") (pinfunction "2_2") (pintype "input"))
      (node (ref "R5") (pin "2") (pinfunction "2_2") (pintype "input"))
      (node (ref "R8") (pin "1") (pinfunction "1_1") (pintype "input"))
      (node (ref "U1") (pin "108") (pinfunction "VDD_108") (pintype "unspecified"))
      (node (ref "U1") (pin "121") (pinfunction "VDD_121") (pintype "unspecified"))
      (node (ref "U1") (pin "131") (pinfunction "VDD_131") (pintype "unspecified"))
      (node (ref "U1") (pin "144") (pinfunction "VDD_144") (pintype "unspecified"))
      (node (ref "U1") (pin "17") (pinfunction "VDD_17") (pintype "unspecified"))
      (node (ref "U1") (pin "30") (pinfunction "VDD_30") (pintype "unspecified"))
      (node (ref "U1") (pin "39") (pinfunction "VDD_39") (pintype "unspecified"))
      (node (ref "U1") (pin "52") (pinfunction "VDD_52") (pintype "unspecified"))
      (node (ref "U1") (pin "6") (pinfunction "VBAT_6") (pintype "unspecified"))
      (node (ref "U1") (pin "62") (pinfunction "VDD_62") (pintype "unspecified"))
      (node (ref "U1") (pin "72") (pinfunction "VDD_72") (pintype "unspecified"))
      (node (ref "U1") (pin "84") (pinfunction "VDD_84") (pintype "unspecified"))
      (node (ref "U1") (pin "95") (pinfunction "VDD_95") (pintype "unspecified"))
    )
    (net (code "65") (name "VDDA") (class "Default")
      (node (ref "C20") (pin "2") (pinfunction "2_2") (pintype "unspecified"))
      (node (ref "U1") (pin "32") (pinfunction "VREF+_32") (pintype "unspecified"))
      (node (ref "U1") (pin "33") (pinfunction "VDDA_33") (pintype "unspecified"))
      (node (ref "U9") (pin "5") (pinfunction "VOUT_5") (pintype "unspecified"))
    )
    (net (code "66") (name "unconnected-(CAN_1-VREF-Pad5)") (class "Default")
      (node (ref "CAN_1") (pin "5") (pinfunction "VREF_5") (pintype "unspecified+no_connect"))
    )
    (net (code "67") (name "unconnected-(CAN_2-VREF-Pad5)") (class "Default")
      (node (ref "CAN_2") (pin "5") (pinfunction "VREF_5") (pintype "unspecified+no_connect"))
    )
    (net (code "68") (name "unconnected-(CN3-Pad3)") (class "Default")
      (node (ref "CN3") (pin "3") (pinfunction "3_3") (pintype "unspecified+no_connect"))
    )
    (net (code "69") (name "unconnected-(CN3-Pad4)") (class "Default")
      (node (ref "CN3") (pin "4") (pinfunction "4_4") (pintype "unspecified+no_connect"))
    )
    (net (code "70") (name "unconnected-(U1-PA0-Pad34)") (class "Default")
      (node (ref "U1") (pin "34") (pinfunction "PA0_34") (pintype "unspecified"))
    )
    (net (code "71") (name "unconnected-(U1-PA1-Pad35)") (class "Default")
      (node (ref "U1") (pin "35") (pinfunction "PA1_35") (pintype "unspecified"))
    )
    (net (code "72") (name "unconnected-(U1-PA8-Pad100)") (class "Default")
      (node (ref "U1") (pin "100") (pinfunction "PA8_100") (pintype "unspecified"))
    )
    (net (code "73") (name "unconnected-(U1-PA11-Pad103)") (class "Default")
      (node (ref "U1") (pin "103") (pinfunction "PA11_103") (pintype "unspecified"))
    )
    (net (code "74") (name "unconnected-(U1-PA12-Pad104)") (class "Default")
      (node (ref "U1") (pin "104") (pinfunction "PA12_104") (pintype "unspecified"))
    )
    (net (code "75") (name "unconnected-(U1-PA15-Pad110)") (class "Default")
      (node (ref "U1") (pin "110") (pinfunction "PA15_110") (pintype "unspecified"))
    )
    (net (code "76") (name "unconnected-(U1-PB0-Pad46)") (class "Default")
      (node (ref "U1") (pin "46") (pinfunction "PB0_46") (pintype "unspecified"))
    )
    (net (code "77") (name "unconnected-(U1-PB1-Pad47)") (class "Default")
      (node (ref "U1") (pin "47") (pinfunction "PB1_47") (pintype "unspecified"))
    )
    (net (code "78") (name "unconnected-(U1-PB3-Pad133)") (class "Default")
      (node (ref "U1") (pin "133") (pinfunction "PB3_133") (pintype "unspecified"))
    )
    (net (code "79") (name "unconnected-(U1-PB4-Pad134)") (class "Default")
      (node (ref "U1") (pin "134") (pinfunction "PB4_134") (pintype "unspecified"))
    )
    (net (code "80") (name "unconnected-(U1-PB5-Pad135)") (class "Default")
      (node (ref "U1") (pin "135") (pinfunction "PB5_135") (pintype "unspecified"))
    )
    (net (code "81") (name "unconnected-(U1-PB14-Pad75)") (class "Default")
      (node (ref "U1") (pin "75") (pinfunction "PB14_75") (pintype "unspecified"))
    )
    (net (code "82") (name "unconnected-(U1-PB15-Pad76)") (class "Default")
      (node (ref "U1") (pin "76") (pinfunction "PB15_76") (pintype "unspecified"))
    )
    (net (code "83") (name "unconnected-(U1-PC6-Pad96)") (class "Default")
      (node (ref "U1") (pin "96") (pinfunction "PC6_96") (pintype "unspecified"))
    )
    (net (code "84") (name "unconnected-(U1-PC7-Pad97)") (class "Default")
      (node (ref "U1") (pin "97") (pinfunction "PC7_97") (pintype "unspecified"))
    )
    (net (code "85") (name "unconnected-(U1-PC8-Pad98)") (class "Default")
      (node (ref "U1") (pin "98") (pinfunction "PC8_98") (pintype "unspecified"))
    )
    (net (code "86") (name "unconnected-(U1-PC9-Pad99)") (class "Default")
      (node (ref "U1") (pin "99") (pinfunction "PC9_99") (pintype "unspecified"))
    )
    (net (code "87") (name "unconnected-(U1-PC13-Pad7)") (class "Default")
      (node (ref "U1") (pin "7") (pinfunction "PC13_7") (pintype "unspecified"))
    )
    (net (code "88") (name "unconnected-(U1-PC14-Pad8)") (class "Default")
      (node (ref "U1") (pin "8") (pinfunction "PC14_8") (pintype "unspecified"))
    )
    (net (code "89") (name "unconnected-(U1-PC15-Pad9)") (class "Default")
      (node (ref "U1") (pin "9") (pinfunction "PC15_9") (pintype "unspecified"))
    )
    (net (code "90") (name "unconnected-(U1-PD3-Pad117)") (class "Default")
      (node (ref "U1") (pin "117") (pinfunction "PD3_117") (pintype "unspecified"))
    )
    (net (code "91") (name "unconnected-(U1-PD4-Pad118)") (class "Default")
      (node (ref "U1") (pin "118") (pinfunction "PD4_118") (pintype "unspecified"))
    )
    (net (code "92") (name "unconnected-(U1-PD5-Pad119)") (class "Default")
      (node (ref "U1") (pin "119") (pinfunction "PD5_119") (pintype "unspecified"))
    )
    (net (code "93") (name "unconnected-(U1-PD6-Pad122)") (class "Default")
      (node (ref "U1") (pin "122") (pinfunction "PD6_122") (pintype "unspecified"))
    )
    (net (code "94") (name "unconnected-(U1-PD7-Pad123)") (class "Default")
      (node (ref "U1") (pin "123") (pinfunction "PD7_123") (pintype "unspecified"))
    )
    (net (code "95") (name "unconnected-(U1-PD8-Pad77)") (class "Default")
      (node (ref "U1") (pin "77") (pinfunction "PD8_77") (pintype "unspecified"))
    )
    (net (code "96") (name "unconnected-(U1-PD9-Pad78)") (class "Default")
      (node (ref "U1") (pin "78") (pinfunction "PD9_78") (pintype "unspecified"))
    )
    (net (code "97") (name "unconnected-(U1-PD10-Pad79)") (class "Default")
      (node (ref "U1") (pin "79") (pinfunction "PD10_79") (pintype "unspecified"))
    )
    (net (code "98") (name "unconnected-(U1-PD11-Pad80)") (class "Default")
      (node (ref "U1") (pin "80") (pinfunction "PD11_80") (pintype "unspecified"))
    )
    (net (code "99") (name "unconnected-(U1-PD12-Pad81)") (class "Default")
      (node (ref "U1") (pin "81") (pinfunction "PD12_81") (pintype "unspecified"))
    )
    (net (code "100") (name "unconnected-(U1-PD13-Pad82)") (class "Default")
      (node (ref "U1") (pin "82") (pinfunction "PD13_82") (pintype "unspecified"))
    )
    (net (code "101") (name "unconnected-(U1-PD14-Pad85)") (class "Default")
      (node (ref "U1") (pin "85") (pinfunction "PD14_85") (pintype "unspecified"))
    )
    (net (code "102") (name "unconnected-(U1-PD15-Pad86)") (class "Default")
      (node (ref "U1") (pin "86") (pinfunction "PD15_86") (pintype "unspecified"))
    )
    (net (code "103") (name "unconnected-(U1-PE0-Pad141)") (class "Default")
      (node (ref "U1") (pin "141") (pinfunction "PE0_141") (pintype "unspecified"))
    )
    (net (code "104") (name "unconnected-(U1-PE1-Pad142)") (class "Default")
      (node (ref "U1") (pin "142") (pinfunction "PE1_142") (pintype "unspecified"))
    )
    (net (code "105") (name "unconnected-(U1-PE2-Pad1)") (class "Default")
      (node (ref "U1") (pin "1") (pinfunction "PE2_1") (pintype "unspecified"))
    )
    (net (code "106") (name "unconnected-(U1-PE3-Pad2)") (class "Default")
      (node (ref "U1") (pin "2") (pinfunction "PE3_2") (pintype "unspecified"))
    )
    (net (code "107") (name "unconnected-(U1-PE4-Pad3)") (class "Default")
      (node (ref "U1") (pin "3") (pinfunction "PE4_3") (pintype "unspecified"))
    )
    (net (code "108") (name "unconnected-(U1-PE5-Pad4)") (class "Default")
      (node (ref "U1") (pin "4") (pinfunction "PE5_4") (pintype "unspecified"))
    )
    (net (code "109") (name "unconnected-(U1-PE6-Pad5)") (class "Default")
      (node (ref "U1") (pin "5") (pinfunction "PE6_5") (pintype "unspecified"))
    )
    (net (code "110") (name "unconnected-(U1-PE7-Pad58)") (class "Default")
      (node (ref "U1") (pin "58") (pinfunction "PE7_58") (pintype "unspecified"))
    )
    (net (code "111") (name "unconnected-(U1-PE8-Pad59)") (class "Default")
      (node (ref "U1") (pin "59") (pinfunction "PE8_59") (pintype "unspecified"))
    )
    (net (code "112") (name "unconnected-(U1-PE9-Pad60)") (class "Default")
      (node (ref "U1") (pin "60") (pinfunction "PE9_60") (pintype "unspecified"))
    )
    (net (code "113") (name "unconnected-(U1-PE10-Pad63)") (class "Default")
      (node (ref "U1") (pin "63") (pinfunction "PE10_63") (pintype "unspecified"))
    )
    (net (code "114") (name "unconnected-(U1-PE11-Pad64)") (class "Default")
      (node (ref "U1") (pin "64") (pinfunction "PE11_64") (pintype "unspecified"))
    )
    (net (code "115") (name "unconnected-(U1-PE12-Pad65)") (class "Default")
      (node (ref "U1") (pin "65") (pinfunction "PE12_65") (pintype "unspecified"))
    )
    (net (code "116") (name "unconnected-(U1-PE13-Pad66)") (class "Default")
      (node (ref "U1") (pin "66") (pinfunction "PE13_66") (pintype "unspecified"))
    )
    (net (code "117") (name "unconnected-(U1-PE14-Pad67)") (class "Default")
      (node (ref "U1") (pin "67") (pinfunction "PE14_67") (pintype "unspecified"))
    )
    (net (code "118") (name "unconnected-(U1-PE15-Pad68)") (class "Default")
      (node (ref "U1") (pin "68") (pinfunction "PE15_68") (pintype "unspecified"))
    )
    (net (code "119") (name "unconnected-(U1-PF0-Pad10)") (class "Default")
      (node (ref "U1") (pin "10") (pinfunction "PF0_10") (pintype "unspecified"))
    )
    (net (code "120") (name "unconnected-(U1-PF1-Pad11)") (class "Default")
      (node (ref "U1") (pin "11") (pinfunction "PF1_11") (pintype "unspecified"))
    )
    (net (code "121") (name "unconnected-(U1-PF2-Pad12)") (class "Default")
      (node (ref "U1") (pin "12") (pinfunction "PF2_12") (pintype "unspecified"))
    )
    (net (code "122") (name "unconnected-(U1-PF3-Pad13)") (class "Default")
      (node (ref "U1") (pin "13") (pinfunction "PF3_13") (pintype "unspecified"))
    )
    (net (code "123") (name "unconnected-(U1-PF4-Pad14)") (class "Default")
      (node (ref "U1") (pin "14") (pinfunction "PF4_14") (pintype "unspecified"))
    )
    (net (code "124") (name "unconnected-(U1-PF5-Pad15)") (class "Default")
      (node (ref "U1") (pin "15") (pinfunction "PF5_15") (pintype "unspecified"))
    )
    (net (code "125") (name "unconnected-(U1-PF6-Pad18)") (class "Default")
      (node (ref "U1") (pin "18") (pinfunction "PF6_18") (pintype "unspecified"))
    )
    (net (code "126") (name "unconnected-(U1-PF7-Pad19)") (class "Default")
      (node (ref "U1") (pin "19") (pinfunction "PF7_19") (pintype "unspecified"))
    )
    (net (code "127") (name "unconnected-(U1-PF8-Pad20)") (class "Default")
      (node (ref "U1") (pin "20") (pinfunction "PF8_20") (pintype "unspecified"))
    )
    (net (code "128") (name "unconnected-(U1-PF9-Pad21)") (class "Default")
      (node (ref "U1") (pin "21") (pinfunction "PF9_21") (pintype "unspecified"))
    )
    (net (code "129") (name "unconnected-(U1-PF10-Pad22)") (class "Default")
      (node (ref "U1") (pin "22") (pinfunction "PF10_22") (pintype "unspecified"))
    )
    (net (code "130") (name "unconnected-(U1-PF11-Pad49)") (class "Default")
      (node (ref "U1") (pin "49") (pinfunction "PF11_49") (pintype "unspecified"))
    )
    (net (code "131") (name "unconnected-(U1-PF12-Pad50)") (class "Default")
      (node (ref "U1") (pin "50") (pinfunction "PF12_50") (pintype "unspecified"))
    )
    (net (code "132") (name "unconnected-(U1-PF13-Pad53)") (class "Default")
      (node (ref "U1") (pin "53") (pinfunction "PF13_53") (pintype "unspecified"))
    )
    (net (code "133") (name "unconnected-(U1-PF14-Pad54)") (class "Default")
      (node (ref "U1") (pin "54") (pinfunction "PF14_54") (pintype "unspecified"))
    )
    (net (code "134") (name "unconnected-(U1-PF15-Pad55)") (class "Default")
      (node (ref "U1") (pin "55") (pinfunction "PF15_55") (pintype "unspecified"))
    )
    (net (code "135") (name "unconnected-(U1-PG0-Pad56)") (class "Default")
      (node (ref "U1") (pin "56") (pinfunction "PG0_56") (pintype "unspecified"))
    )
    (net (code "136") (name "unconnected-(U1-PG1-Pad57)") (class "Default")
      (node (ref "U1") (pin "57") (pinfunction "PG1_57") (pintype "unspecified"))
    )
    (net (code "137") (name "unconnected-(U1-PG2-Pad87)") (class "Default")
      (node (ref "U1") (pin "87") (pinfunction "PG2_87") (pintype "unspecified"))
    )
    (net (code "138") (name "unconnected-(U1-PG3-Pad88)") (class "Default")
      (node (ref "U1") (pin "88") (pinfunction "PG3_88") (pintype "unspecified"))
    )
    (net (code "139") (name "unconnected-(U1-PG4-Pad89)") (class "Default")
      (node (ref "U1") (pin "89") (pinfunction "PG4_89") (pintype "unspecified"))
    )
    (net (code "140") (name "unconnected-(U1-PG5-Pad90)") (class "Default")
      (node (ref "U1") (pin "90") (pinfunction "PG5_90") (pintype "unspecified"))
    )
    (net (code "141") (name "unconnected-(U1-PG6-Pad91)") (class "Default")
      (node (ref "U1") (pin "91") (pinfunction "PG6_91") (pintype "unspecified"))
    )
    (net (code "142") (name "unconnected-(U1-PG7-Pad92)") (class "Default")
      (node (ref "U1") (pin "92") (pinfunction "PG7_92") (pintype "unspecified"))
    )
    (net (code "143") (name "unconnected-(U1-PG8-Pad93)") (class "Default")
      (node (ref "U1") (pin "93") (pinfunction "PG8_93") (pintype "unspecified"))
    )
    (net (code "144") (name "unconnected-(U1-PG10-Pad125)") (class "Default")
      (node (ref "U1") (pin "125") (pinfunction "PG10_125") (pintype "unspecified"))
    )
    (net (code "145") (name "unconnected-(U1-PG11-Pad126)") (class "Default")
      (node (ref "U1") (pin "126") (pinfunction "PG11_126") (pintype "unspecified"))
    )
    (net (code "146") (name "unconnected-(U1-PG12-Pad127)") (class "Default")
      (node (ref "U1") (pin "127") (pinfunction "PG12_127") (pintype "unspecified"))
    )
    (net (code "147") (name "unconnected-(U1-PG13-Pad128)") (class "Default")
      (node (ref "U1") (pin "128") (pinfunction "PG13_128") (pintype "unspecified"))
    )
    (net (code "148") (name "unconnected-(U1-PG15-Pad132)") (class "Default")
      (node (ref "U1") (pin "132") (pinfunction "PG15_132") (pintype "unspecified"))
    )
    (net (code "149") (name "unconnected-(U1-VSS-Pad130)") (class "Default")
      (node (ref "U1") (pin "130") (pinfunction "VSS_130") (pintype "unspecified"))
    )
    (net (code "150") (name "unconnected-(U5-NC-Pad4)") (class "Default")
      (node (ref "U5") (pin "4") (pinfunction "NC_4") (pintype "unspecified+no_connect"))
    )
    (net (code "151") (name "unconnected-(U6-EN-Pad5)") (class "Default")
      (node (ref "U6") (pin "5") (pinfunction "EN_5") (pintype "unspecified+no_connect"))
    )
  )
)
